# IR_beacon.net
KiCad netlist of a schematic drawn in EAGLE
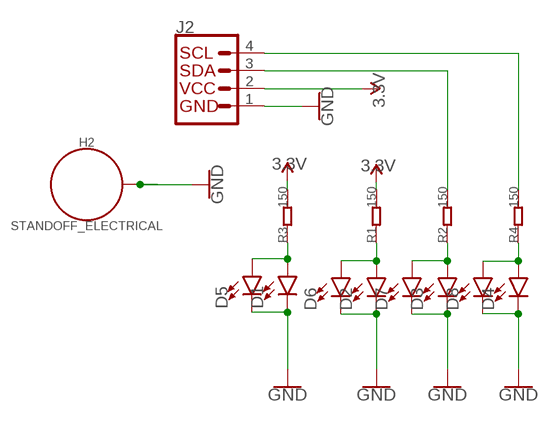
[diagram p0: schematic, sheet 1]

(export (version "E")
  (design (tool "Eeschema 10.0.6"))
  (components
    (comp (ref "D1")
      (value "LED-FKIT-1206")
      (footprint "eagle-import:FKIT-LED-1206")
      (libsource (lib "eagle-import") (part "LED-FKIT-1206"))
    )
    (comp (ref "D2")
      (value "LED-FKIT-1206")
      (footprint "eagle-import:FKIT-LED-1206")
      (libsource (lib "eagle-import") (part "LED-FKIT-1206"))
    )
    (comp (ref "D3")
      (value "LED-FKIT-1206")
      (footprint "eagle-import:FKIT-LED-1206")
      (libsource (lib "eagle-import") (part "LED-FKIT-1206"))
    )
    (comp (ref "D4")
      (value "LED-FKIT-1206")
      (footprint "eagle-import:FKIT-LED-1206")
      (libsource (lib "eagle-import") (part "LED-FKIT-1206"))
    )
    (comp (ref "D5")
      (value "LED-FKIT-1206")
      (footprint "eagle-import:FKIT-LED-1206")
      (libsource (lib "eagle-import") (part "LED-FKIT-1206"))
    )
    (comp (ref "D6")
      (value "LED-FKIT-1206")
      (footprint "eagle-import:FKIT-LED-1206")
      (libsource (lib "eagle-import") (part "LED-FKIT-1206"))
    )
    (comp (ref "D7")
      (value "LED-FKIT-1206")
      (footprint "eagle-import:FKIT-LED-1206")
      (libsource (lib "eagle-import") (part "LED-FKIT-1206"))
    )
    (comp (ref "D8")
      (value "LED-FKIT-1206")
      (footprint "eagle-import:FKIT-LED-1206")
      (libsource (lib "eagle-import") (part "LED-FKIT-1206"))
    )
    (comp (ref "H2")
      (value "STANDOFF_ELECTRICAL")
      (footprint "eagle-import:STANDOFF-ELECTRICAL")
      (libsource (lib "eagle-import") (part "STANDOFF_ELECTRICAL"))
    )
    (comp (ref "J2")
      (value "QWIIC_CONNECTORJS-1MM")
      (footprint "eagle-import:1X04_1MM_RA")
      (libsource (lib "eagle-import") (part "QWIIC_CONNECTORJS-1MM"))
    )
    (comp (ref "R1")
      (value "150")
      (footprint "eagle-import:0603_S")
      (libsource (lib "eagle-import") (part "005-R0603_S"))
    )
    (comp (ref "R2")
      (value "150")
      (footprint "eagle-import:0603_S")
      (libsource (lib "eagle-import") (part "005-R0603_S"))
    )
    (comp (ref "R3")
      (value "150")
      (footprint "eagle-import:0603_S")
      (libsource (lib "eagle-import") (part "005-R0603_S"))
    )
    (comp (ref "R4")
      (value "150")
      (footprint "eagle-import:0603_S")
      (libsource (lib "eagle-import") (part "005-R0603_S"))
    )
  )
  (nets
    (net (code "1") (name "3.3V") (class "Default")
      (node (ref "J2") (pin "2") (pinfunction "2_2") (pintype "power_in"))
      (node (ref "R1") (pin "2") (pinfunction "2_2") (pintype "passive"))
      (node (ref "R3") (pin "2") (pinfunction "2_2") (pintype "passive"))
    )
    (net (code "2") (name "GND") (class "Default")
      (node (ref "D1") (pin "C") (pinfunction "C_C") (pintype "passive"))
      (node (ref "D2") (pin "C") (pinfunction "C_C") (pintype "passive"))
      (node (ref "D3") (pin "C") (pinfunction "C_C") (pintype "passive"))
      (node (ref "D4") (pin "C") (pinfunction "C_C") (pintype "passive"))
      (node (ref "D5") (pin "C") (pinfunction "C_C") (pintype "passive"))
      (node (ref "D6") (pin "C") (pinfunction "C_C") (pintype "passive"))
      (node (ref "D7") (pin "C") (pinfunction "C_C") (pintype "passive"))
      (node (ref "D8") (pin "C") (pinfunction "C_C") (pintype "passive"))
      (node (ref "H2") (pin "P1") (pinfunction "P$1_P1") (pintype "bidirectional"))
      (node (ref "J2") (pin "1") (pinfunction "1_1") (pintype "power_in"))
    )
    (net (code "3") (name "Net-(D1-PadA)") (class "Default")
      (node (ref "D1") (pin "A") (pinfunction "A_A") (pintype "passive"))
      (node (ref "D5") (pin "A") (pinfunction "A_A") (pintype "passive"))
      (node (ref "R3") (pin "1") (pinfunction "1_1") (pintype "passive"))
    )
    (net (code "4") (name "Net-(D2-PadA)") (class "Default")
      (node (ref "D2") (pin "A") (pinfunction "A_A") (pintype "passive"))
      (node (ref "D6") (pin "A") (pinfunction "A_A") (pintype "passive"))
      (node (ref "R1") (pin "1") (pinfunction "1_1") (pintype "passive"))
    )
    (net (code "5") (name "Net-(D3-PadA)") (class "Default")
      (node (ref "D3") (pin "A") (pinfunction "A_A") (pintype "passive"))
      (node (ref "D7") (pin "A") (pinfunction "A_A") (pintype "passive"))
      (node (ref "R2") (pin "1") (pinfunction "1_1") (pintype "passive"))
    )
    (net (code "6") (name "Net-(D4-PadA)") (class "Default")
      (node (ref "D4") (pin "A") (pinfunction "A_A") (pintype "passive"))
      (node (ref "D8") (pin "A") (pinfunction "A_A") (pintype "passive"))
      (node (ref "R4") (pin "1") (pinfunction "1_1") (pintype "passive"))
    )
    (net (code "7") (name "Net-(J2-Pad3)") (class "Default")
      (node (ref "J2") (pin "3") (pinfunction "3_3") (pintype "passive"))
      (node (ref "R2") (pin "2") (pinfunction "2_2") (pintype "passive"))
    )
    (net (code "8") (name "Net-(J2-Pad4)") (class "Default")
      (node (ref "J2") (pin "4") (pinfunction "4_4") (pintype "passive"))
      (node (ref "R4") (pin "2") (pinfunction "2_2") (pintype "passive"))
    )
  )
)
